# 7segement2digits1badidea-mk-2.net
KiCad netlist of a schematic drawn in EAGLE
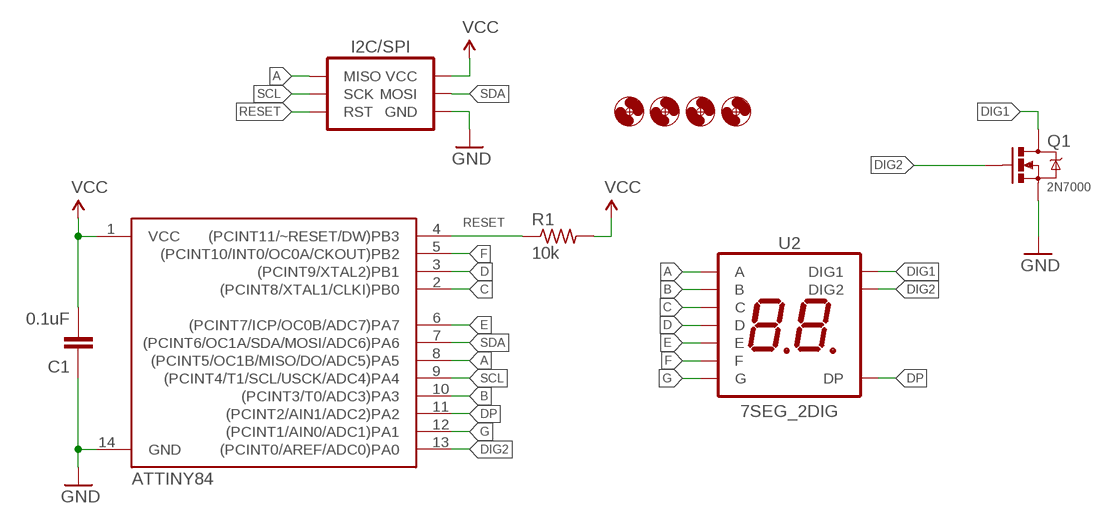
[diagram p0: schematic, sheet 1]

(export (version "E")
  (design (tool "Eeschema 10.0.6"))
  (components
    (comp (ref "C1")
      (value "0.1uF")
      (footprint "eagle-import:C0805")
      (libsource (lib "eagle-import") (part "CAPACITOR-CERAMICC0805"))
    )
    (comp (ref "H1")
      (value "HOLE#2")
      (footprint "eagle-import:HOLE-#2")
      (libsource (lib "eagle-import") (part "HOLE#2"))
    )
    (comp (ref "H2")
      (value "HOLE#2")
      (footprint "eagle-import:HOLE-#2")
      (libsource (lib "eagle-import") (part "HOLE#2"))
    )
    (comp (ref "H3")
      (value "HOLE#2")
      (footprint "eagle-import:HOLE-#2")
      (libsource (lib "eagle-import") (part "HOLE#2"))
    )
    (comp (ref "H4")
      (value "HOLE#2")
      (footprint "eagle-import:HOLE-#2")
      (libsource (lib "eagle-import") (part "HOLE#2"))
    )
    (comp (ref "I2C/SPI")
      (value "AVR_SPI_PRG_6PTH_INLINE_I2C")
      (footprint "eagle-import:AVR_ISP_INLINE_PTH_I2C")
      (libsource (lib "eagle-import") (part "AVR_SPI_PRG_6PTH_INLINE_I2C"))
    )
    (comp (ref "Q1")
      (value "2N7000")
      (footprint "eagle-import:SOT23")
      (libsource (lib "eagle-import") (part "MOSFET-NCHANNELBSS123LT1G"))
    )
    (comp (ref "R1")
      (value "10k")
      (footprint "eagle-import:R0805")
      (libsource (lib "eagle-import") (part "RESISTORR0805"))
    )
    (comp (ref "U1")
      (value "ATTINY84")
      (footprint "eagle-import:SO14")
      (libsource (lib "eagle-import") (part "ATTINY84"))
    )
    (comp (ref "U2")
      (value "7SEG_2DIG")
      (footprint "eagle-import:7SEG_2DIG_14MM")
      (libsource (lib "eagle-import") (part "7SEG_2DIG"))
    )
  )
  (nets
    (net (code "1") (name "A") (class "Default")
      (node (ref "I2C/SPI") (pin "MISO") (pinfunction "MISO_MISO") (pintype "passive"))
      (node (ref "U1") (pin "8") (pinfunction "(PCINT5/OC1B/MISO/DO/ADC5)PA5_8") (pintype "bidirectional"))
      (node (ref "U2") (pin "4") (pinfunction "A_4") (pintype "passive"))
    )
    (net (code "2") (name "B") (class "Default")
      (node (ref "U1") (pin "10") (pinfunction "(PCINT3/T0/ADC3)PA3_10") (pintype "bidirectional"))
      (node (ref "U2") (pin "3") (pinfunction "B_3") (pintype "passive"))
    )
    (net (code "3") (name "C") (class "Default")
      (node (ref "U1") (pin "2") (pinfunction "(PCINT8/XTAL1/CLKI)PB0_2") (pintype "bidirectional"))
      (node (ref "U2") (pin "9") (pinfunction "C_9") (pintype "passive"))
    )
    (net (code "4") (name "D") (class "Default")
      (node (ref "U1") (pin "3") (pinfunction "(PCINT9/XTAL2)PB1_3") (pintype "bidirectional"))
      (node (ref "U2") (pin "8") (pinfunction "D_8") (pintype "passive"))
    )
    (net (code "5") (name "DIG1") (class "Default")
      (node (ref "Q1") (pin "3") (pinfunction "D_3") (pintype "passive"))
      (node (ref "U2") (pin "5") (pinfunction "DIG1_5") (pintype "passive"))
    )
    (net (code "6") (name "DIG2") (class "Default")
      (node (ref "Q1") (pin "1") (pinfunction "G_1") (pintype "passive"))
      (node (ref "U1") (pin "13") (pinfunction "(PCINT0/AREF/ADC0)PA0_13") (pintype "bidirectional"))
      (node (ref "U2") (pin "10") (pinfunction "DIG2_10") (pintype "passive"))
    )
    (net (code "7") (name "DP") (class "Default")
      (node (ref "U1") (pin "11") (pinfunction "(PCINT2/AIN1/ADC2)PA2_11") (pintype "bidirectional"))
      (node (ref "U2") (pin "2") (pinfunction "DP_2") (pintype "passive"))
    )
    (net (code "8") (name "E") (class "Default")
      (node (ref "U1") (pin "6") (pinfunction "(PCINT7/ICP/OC0B/ADC7)PA7_6") (pintype "bidirectional"))
      (node (ref "U2") (pin "6") (pinfunction "E_6") (pintype "passive"))
    )
    (net (code "9") (name "F") (class "Default")
      (node (ref "U1") (pin "5") (pinfunction "(PCINT10/INT0/OC0A/CKOUT)PB2_5") (pintype "bidirectional"))
      (node (ref "U2") (pin "7") (pinfunction "F_7") (pintype "passive"))
    )
    (net (code "10") (name "G") (class "Default")
      (node (ref "U1") (pin "12") (pinfunction "(PCINT1/AIN0/ADC1)PA1_12") (pintype "bidirectional"))
      (node (ref "U2") (pin "1") (pinfunction "G_1") (pintype "passive"))
    )
    (net (code "11") (name "GND") (class "Default")
      (node (ref "C1") (pin "1") (pinfunction "1_1") (pintype "passive"))
      (node (ref "I2C/SPI") (pin "GND") (pinfunction "GND_GND") (pintype "passive"))
      (node (ref "Q1") (pin "2") (pinfunction "S_2") (pintype "passive"))
      (node (ref "U1") (pin "14") (pinfunction "GND_14") (pintype "bidirectional"))
    )
    (net (code "12") (name "RESET") (class "Default")
      (node (ref "I2C/SPI") (pin "RESET") (pinfunction "RST_RESET") (pintype "passive"))
      (node (ref "R1") (pin "1") (pinfunction "1_1") (pintype "passive"))
      (node (ref "U1") (pin "4") (pinfunction "(PCINT11/~{RESET/DW})PB3_4") (pintype "bidirectional"))
    )
    (net (code "13") (name "SCL") (class "Default")
      (node (ref "I2C/SPI") (pin "SCK") (pinfunction "SCK_SCK") (pintype "passive"))
      (node (ref "U1") (pin "9") (pinfunction "(PCINT4/T1/SCL/USCK/ADC4)PA4_9") (pintype "bidirectional"))
    )
    (net (code "14") (name "SDA") (class "Default")
      (node (ref "I2C/SPI") (pin "MOSI") (pinfunction "MOSI_MOSI") (pintype "passive"))
      (node (ref "U1") (pin "7") (pinfunction "(PCINT6/OC1A/SDA/MOSI/ADC6)PA6_7") (pintype "bidirectional"))
    )
    (net (code "15") (name "VCC") (class "Default")
      (node (ref "C1") (pin "2") (pinfunction "2_2") (pintype "passive"))
      (node (ref "I2C/SPI") (pin "VCC") (pinfunction "VCC_VCC") (pintype "passive"))
      (node (ref "R1") (pin "2") (pinfunction "2_2") (pintype "passive"))
      (node (ref "U1") (pin "1") (pinfunction "VCC_1") (pintype "bidirectional"))
    )
  )
)
